# OZ440-SE100-CAR003_sheet5.net
KiCad netlist of a schematic drawn in Altium Designer
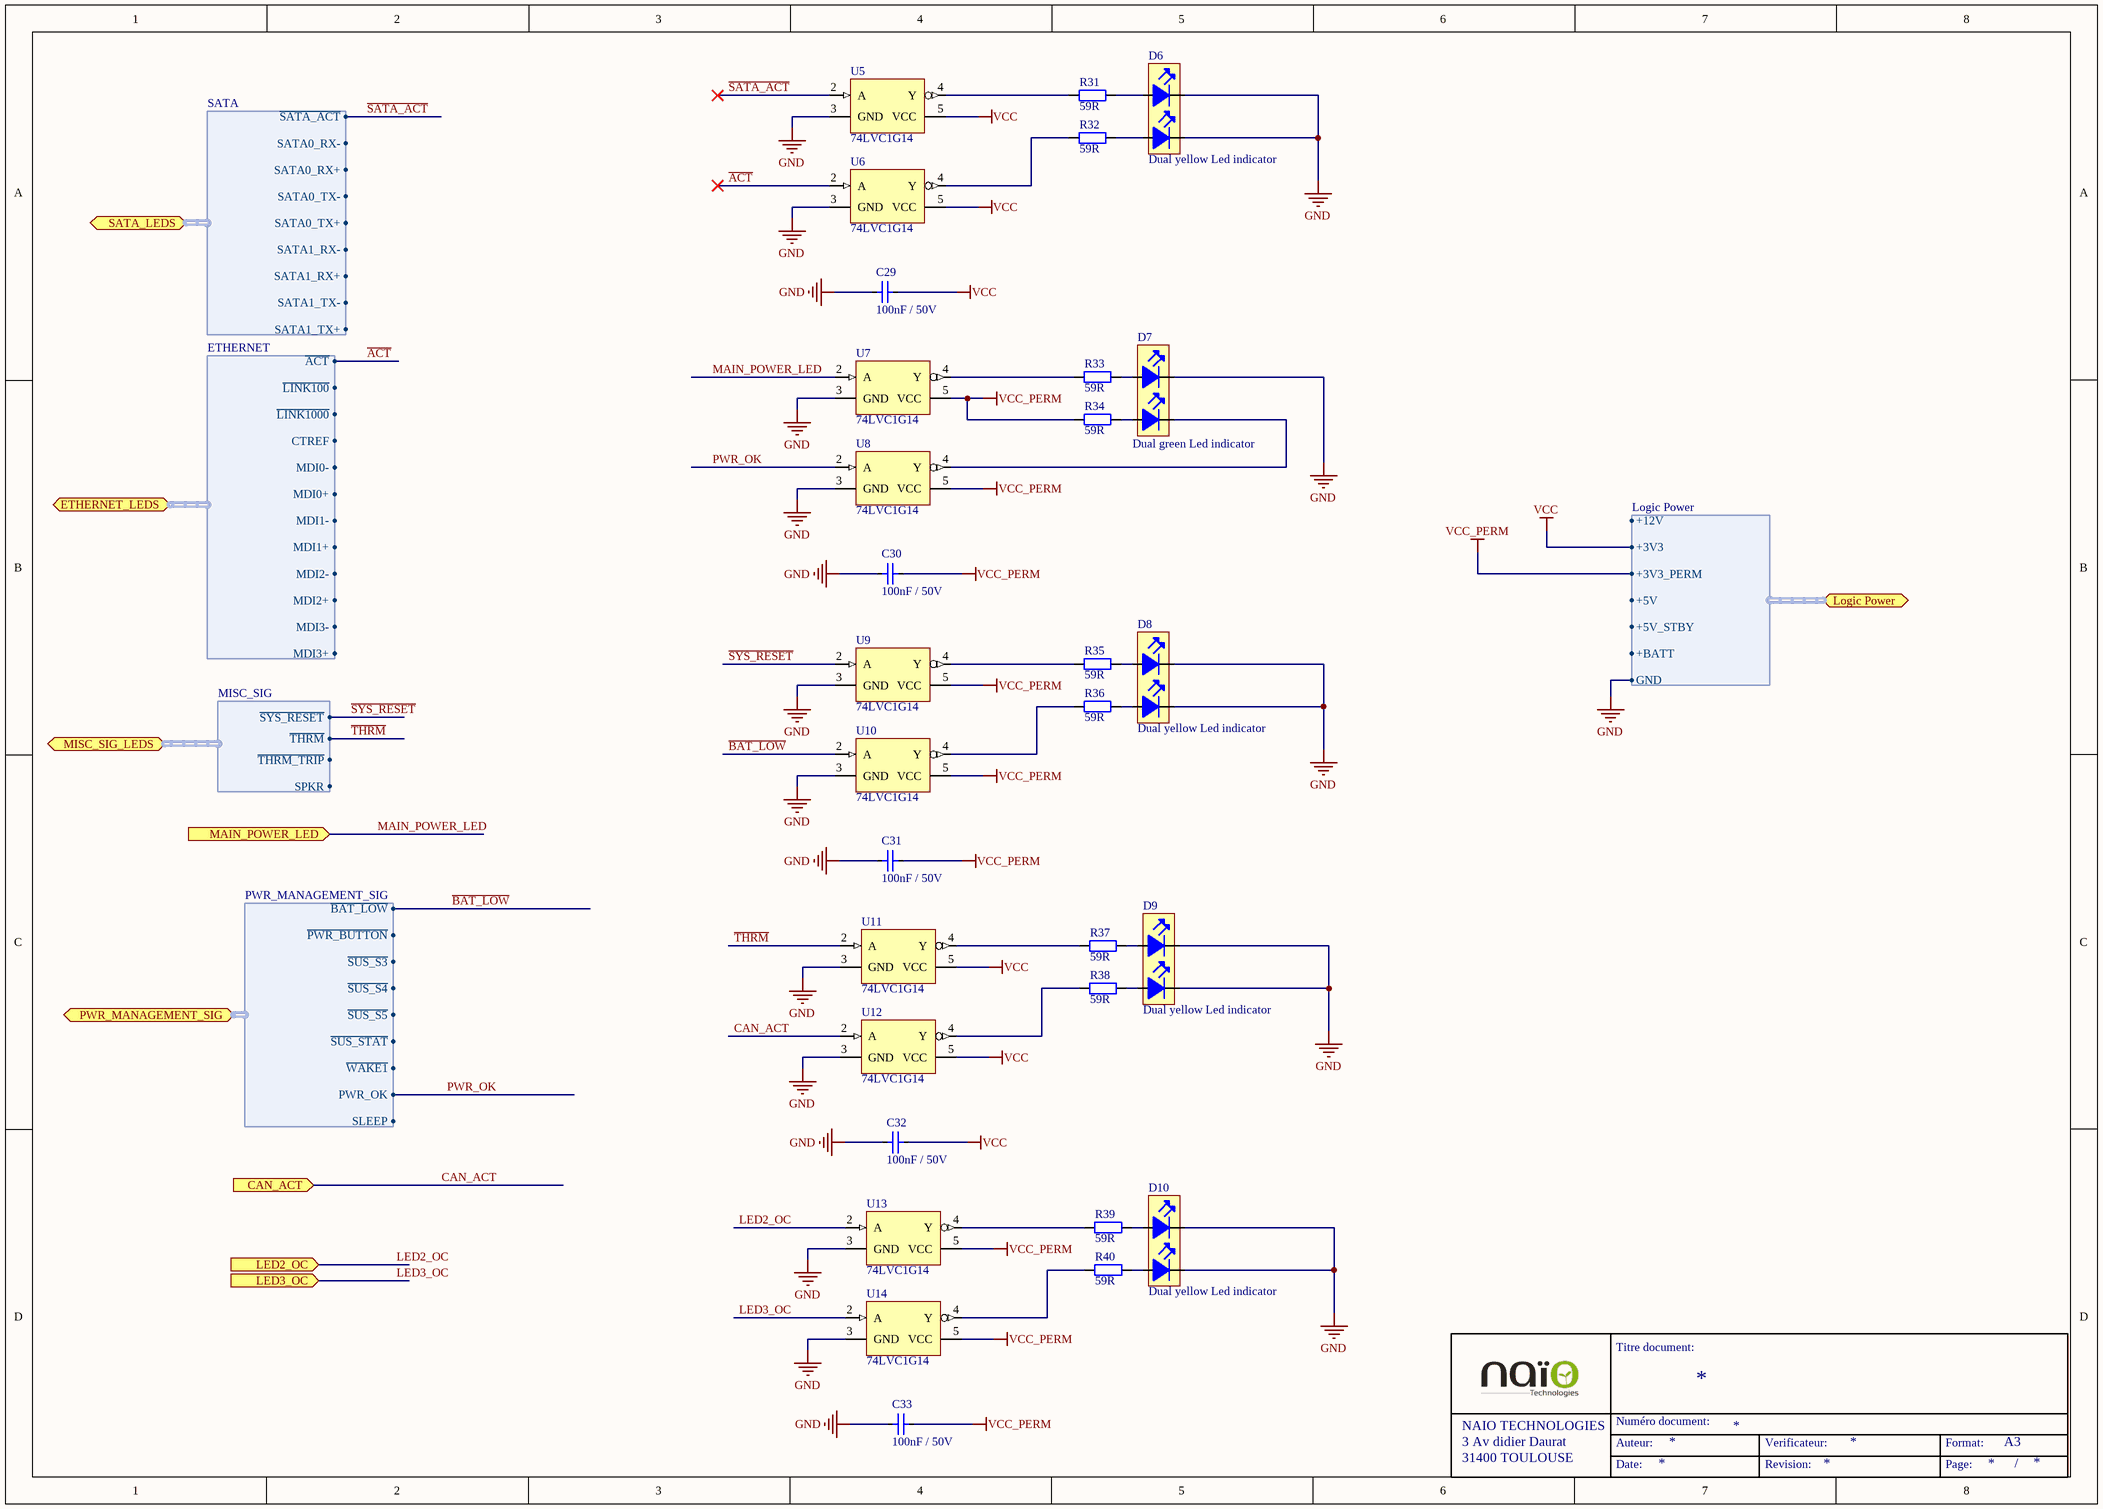
[diagram p0: OZ440-SE100-CAR003_sheet5.SchDoc]

(export (version "E")
  (design (tool "Eeschema 10.0.6"))
  (components
    (comp (ref "C29")
      (value "CAP-SMD")
      (footprint "C0805-STD")
      (description "0805 100nF / 50V  X7R ceramic capacitor")
      (fields
        (field (name "DISPLAYED REFERENCE") "100nF / 50V")
        (field (name "TOLERANCE") "+/- 10%")
        (field (name "MANUFACTURER") "vishay")
      )
      (libsource (lib "lib_NAIO") (part "CAP-SMD"))
    )
    (comp (ref "C30")
      (value "CAP-SMD")
      (footprint "C0805-STD")
      (description "0805 100nF / 50V  X7R ceramic capacitor")
      (fields
        (field (name "DISPLAYED REFERENCE") "100nF / 50V")
        (field (name "TOLERANCE") "+/- 10%")
        (field (name "MANUFACTURER") "vishay")
      )
      (libsource (lib "lib_NAIO") (part "CAP-SMD"))
    )
    (comp (ref "C31")
      (value "CAP-SMD")
      (footprint "C0805-STD")
      (description "0805 100nF / 50V  X7R ceramic capacitor")
      (fields
        (field (name "DISPLAYED REFERENCE") "100nF / 50V")
        (field (name "TOLERANCE") "+/- 10%")
        (field (name "MANUFACTURER") "vishay")
      )
      (libsource (lib "lib_NAIO") (part "CAP-SMD"))
    )
    (comp (ref "C32")
      (value "CAP-SMD")
      (footprint "C0805-STD")
      (description "0805 100nF / 50V  X7R ceramic capacitor")
      (fields
        (field (name "DISPLAYED REFERENCE") "100nF / 50V")
        (field (name "TOLERANCE") "+/- 10%")
        (field (name "MANUFACTURER") "vishay")
      )
      (libsource (lib "lib_NAIO") (part "CAP-SMD"))
    )
    (comp (ref "C33")
      (value "CAP-SMD")
      (footprint "C0805-STD")
      (description "0805 100nF / 50V  X7R ceramic capacitor")
      (fields
        (field (name "DISPLAYED REFERENCE") "100nF / 50V")
        (field (name "TOLERANCE") "+/- 10%")
        (field (name "MANUFACTURER") "vishay")
      )
      (libsource (lib "lib_NAIO") (part "CAP-SMD"))
    )
    (comp (ref "D6")
      (value "LED_DUAL")
      (footprint "LED_3MM_DUAL")
      (description "Dual Yellow led indicator")
      (fields
        (field (name "DISPLAYED REFERENCE") "Dual yellow Led indicator")
        (field (name "MANUFACTURER") "KINGBRIGHT")
      )
      (libsource (lib "lib_NAIO") (part "LED_DUAL"))
    )
    (comp (ref "D7")
      (value "LED_DUAL")
      (footprint "LED_3MM_DUAL")
      (description "Dual green led indicator")
      (fields
        (field (name "DISPLAYED REFERENCE") "Dual green Led indicator")
        (field (name "MANUFACTURER") "KINGBRIGHT")
      )
      (libsource (lib "lib_NAIO") (part "LED_DUAL"))
    )
    (comp (ref "D8")
      (value "LED_DUAL")
      (footprint "LED_3MM_DUAL")
      (description "Dual Yellow led indicator")
      (fields
        (field (name "DISPLAYED REFERENCE") "Dual yellow Led indicator")
        (field (name "MANUFACTURER") "KINGBRIGHT")
      )
      (libsource (lib "lib_NAIO") (part "LED_DUAL"))
    )
    (comp (ref "D9")
      (value "LED_DUAL")
      (footprint "LED_3MM_DUAL")
      (description "Dual Yellow led indicator")
      (fields
        (field (name "DISPLAYED REFERENCE") "Dual yellow Led indicator")
        (field (name "MANUFACTURER") "KINGBRIGHT")
      )
      (libsource (lib "lib_NAIO") (part "LED_DUAL"))
    )
    (comp (ref "D10")
      (value "LED_DUAL")
      (footprint "LED_3MM_DUAL")
      (description "Dual Yellow led indicator")
      (fields
        (field (name "DISPLAYED REFERENCE") "Dual yellow Led indicator")
        (field (name "MANUFACTURER") "KINGBRIGHT")
      )
      (libsource (lib "lib_NAIO") (part "LED_DUAL"))
    )
    (comp (ref "R31")
      (value "RES-SMD")
      (footprint "R0805-STD")
      (description "59 Ohm 0805 SMD resistor")
      (fields
        (field (name "DISPLAYED REFERENCE") "59R")
        (field (name "TOLERANCE") "1 %")
        (field (name "MANUFACTURER") "Vishay")
      )
      (libsource (lib "lib_NAIO") (part "RES-SMD"))
    )
    (comp (ref "R32")
      (value "RES-SMD")
      (footprint "R0805-STD")
      (description "59 Ohm 0805 SMD resistor")
      (fields
        (field (name "DISPLAYED REFERENCE") "59R")
        (field (name "TOLERANCE") "1 %")
        (field (name "MANUFACTURER") "Vishay")
      )
      (libsource (lib "lib_NAIO") (part "RES-SMD"))
    )
    (comp (ref "R33")
      (value "RES-SMD")
      (footprint "R0805-STD")
      (description "59 Ohm 0805 SMD resistor")
      (fields
        (field (name "DISPLAYED REFERENCE") "59R")
        (field (name "TOLERANCE") "1 %")
        (field (name "MANUFACTURER") "Vishay")
      )
      (libsource (lib "lib_NAIO") (part "RES-SMD"))
    )
    (comp (ref "R34")
      (value "RES-SMD")
      (footprint "R0805-STD")
      (description "59 Ohm 0805 SMD resistor")
      (fields
        (field (name "DISPLAYED REFERENCE") "59R")
        (field (name "TOLERANCE") "1 %")
        (field (name "MANUFACTURER") "Vishay")
      )
      (libsource (lib "lib_NAIO") (part "RES-SMD"))
    )
    (comp (ref "R35")
      (value "RES-SMD")
      (footprint "R0805-STD")
      (description "59 Ohm 0805 SMD resistor")
      (fields
        (field (name "DISPLAYED REFERENCE") "59R")
        (field (name "TOLERANCE") "1 %")
        (field (name "MANUFACTURER") "Vishay")
      )
      (libsource (lib "lib_NAIO") (part "RES-SMD"))
    )
    (comp (ref "R36")
      (value "RES-SMD")
      (footprint "R0805-STD")
      (description "59 Ohm 0805 SMD resistor")
      (fields
        (field (name "DISPLAYED REFERENCE") "59R")
        (field (name "TOLERANCE") "1 %")
        (field (name "MANUFACTURER") "Vishay")
      )
      (libsource (lib "lib_NAIO") (part "RES-SMD"))
    )
    (comp (ref "R37")
      (value "RES-SMD")
      (footprint "R0805-STD")
      (description "59 Ohm 0805 SMD resistor")
      (fields
        (field (name "DISPLAYED REFERENCE") "59R")
        (field (name "TOLERANCE") "1 %")
        (field (name "MANUFACTURER") "Vishay")
      )
      (libsource (lib "lib_NAIO") (part "RES-SMD"))
    )
    (comp (ref "R38")
      (value "RES-SMD")
      (footprint "R0805-STD")
      (description "59 Ohm 0805 SMD resistor")
      (fields
        (field (name "DISPLAYED REFERENCE") "59R")
        (field (name "TOLERANCE") "1 %")
        (field (name "MANUFACTURER") "Vishay")
      )
      (libsource (lib "lib_NAIO") (part "RES-SMD"))
    )
    (comp (ref "R39")
      (value "RES-SMD")
      (footprint "R0805-STD")
      (description "59 Ohm 0805 SMD resistor")
      (fields
        (field (name "DISPLAYED REFERENCE") "59R")
        (field (name "TOLERANCE") "1 %")
        (field (name "MANUFACTURER") "Vishay")
      )
      (libsource (lib "lib_NAIO") (part "RES-SMD"))
    )
    (comp (ref "R40")
      (value "RES-SMD")
      (footprint "R0805-STD")
      (description "59 Ohm 0805 SMD resistor")
      (fields
        (field (name "DISPLAYED REFERENCE") "59R")
        (field (name "TOLERANCE") "1 %")
        (field (name "MANUFACTURER") "Vishay")
      )
      (libsource (lib "lib_NAIO") (part "RES-SMD"))
    )
    (comp (ref "U5")
      (value "74xxx1G14GW-SOT353-1")
      (footprint "SOT353-1_5pin-STD")
      (description "smith trigger inverter")
      (fields (field (name "DISPLAYED REFERENCE") "74LVC1G14") (field (name "MANUFACTURER") "NXP"))
      (libsource (lib "lib_NAIO") (part "74xxx1G14GW-SOT353-1"))
    )
    (comp (ref "U6")
      (value "74xxx1G14GW-SOT353-1")
      (footprint "SOT353-1_5pin-STD")
      (description "smith trigger inverter")
      (fields (field (name "DISPLAYED REFERENCE") "74LVC1G14") (field (name "MANUFACTURER") "NXP"))
      (libsource (lib "lib_NAIO") (part "74xxx1G14GW-SOT353-1"))
    )
    (comp (ref "U7")
      (value "74xxx1G14GW-SOT353-1")
      (footprint "SOT353-1_5pin-STD")
      (description "smith trigger inverter")
      (fields (field (name "DISPLAYED REFERENCE") "74LVC1G14") (field (name "MANUFACTURER") "NXP"))
      (libsource (lib "lib_NAIO") (part "74xxx1G14GW-SOT353-1"))
    )
    (comp (ref "U8")
      (value "74xxx1G14GW-SOT353-1")
      (footprint "SOT353-1_5pin-STD")
      (description "smith trigger inverter")
      (fields (field (name "DISPLAYED REFERENCE") "74LVC1G14") (field (name "MANUFACTURER") "NXP"))
      (libsource (lib "lib_NAIO") (part "74xxx1G14GW-SOT353-1"))
    )
    (comp (ref "U9")
      (value "74xxx1G14GW-SOT353-1")
      (footprint "SOT353-1_5pin-STD")
      (description "smith trigger inverter")
      (fields (field (name "DISPLAYED REFERENCE") "74LVC1G14") (field (name "MANUFACTURER") "NXP"))
      (libsource (lib "lib_NAIO") (part "74xxx1G14GW-SOT353-1"))
    )
    (comp (ref "U10")
      (value "74xxx1G14GW-SOT353-1")
      (footprint "SOT353-1_5pin-STD")
      (description "smith trigger inverter")
      (fields (field (name "DISPLAYED REFERENCE") "74LVC1G14") (field (name "MANUFACTURER") "NXP"))
      (libsource (lib "lib_NAIO") (part "74xxx1G14GW-SOT353-1"))
    )
    (comp (ref "U11")
      (value "74xxx1G14GW-SOT353-1")
      (footprint "SOT353-1_5pin-STD")
      (description "smith trigger inverter")
      (fields (field (name "DISPLAYED REFERENCE") "74LVC1G14") (field (name "MANUFACTURER") "NXP"))
      (libsource (lib "lib_NAIO") (part "74xxx1G14GW-SOT353-1"))
    )
    (comp (ref "U12")
      (value "74xxx1G14GW-SOT353-1")
      (footprint "SOT353-1_5pin-STD")
      (description "smith trigger inverter")
      (fields (field (name "DISPLAYED REFERENCE") "74LVC1G14") (field (name "MANUFACTURER") "NXP"))
      (libsource (lib "lib_NAIO") (part "74xxx1G14GW-SOT353-1"))
    )
    (comp (ref "U13")
      (value "74xxx1G14GW-SOT353-1")
      (footprint "SOT353-1_5pin-STD")
      (description "smith trigger inverter")
      (fields (field (name "DISPLAYED REFERENCE") "74LVC1G14") (field (name "MANUFACTURER") "NXP"))
      (libsource (lib "lib_NAIO") (part "74xxx1G14GW-SOT353-1"))
    )
    (comp (ref "U14")
      (value "74xxx1G14GW-SOT353-1")
      (footprint "SOT353-1_5pin-STD")
      (description "smith trigger inverter")
      (fields (field (name "DISPLAYED REFERENCE") "74LVC1G14") (field (name "MANUFACTURER") "NXP"))
      (libsource (lib "lib_NAIO") (part "74xxx1G14GW-SOT353-1"))
    )
  )
  (nets
    (net (code "7") (name "/ACT") (class "Default")
      (node (ref "U6") (pin "2") (pinfunction "A_2") (pintype "input"))
    )
    (net (code "8") (name "/BAT_LOW") (class "Default")
      (node (ref "U10") (pin "2") (pinfunction "A_2") (pintype "input"))
    )
    (net (code "9") (name "/CAN_ACT") (class "Default")
      (node (ref "U12") (pin "2") (pinfunction "A_2") (pintype "input"))
    )
    (net (code "10") (name "/LED2_OC") (class "Default")
      (node (ref "U13") (pin "2") (pinfunction "A_2") (pintype "input"))
    )
    (net (code "11") (name "/LED3_OC") (class "Default")
      (node (ref "U14") (pin "2") (pinfunction "A_2") (pintype "input"))
    )
    (net (code "12") (name "/MAIN_POWER_LED") (class "Default")
      (node (ref "U7") (pin "2") (pinfunction "A_2") (pintype "input"))
    )
    (net (code "13") (name "/PWR_OK") (class "Default")
      (node (ref "U8") (pin "2") (pinfunction "A_2") (pintype "input"))
    )
    (net (code "14") (name "/SATA_ACT") (class "Default")
      (node (ref "U5") (pin "2") (pinfunction "A_2") (pintype "input+no_connect"))
    )
    (net (code "15") (name "/SYS_RESET") (class "Default")
      (node (ref "U9") (pin "2") (pinfunction "A_2") (pintype "input"))
    )
    (net (code "16") (name "/THRM") (class "Default")
      (node (ref "U11") (pin "2") (pinfunction "A_2") (pintype "input"))
    )
    (net (code "22") (name "GND") (class "Default")
      (node (ref "C29") (pin "1") (pinfunction "1_1") (pintype "passive"))
      (node (ref "C30") (pin "1") (pinfunction "1_1") (pintype "passive"))
      (node (ref "C31") (pin "1") (pinfunction "1_1") (pintype "passive"))
      (node (ref "C32") (pin "1") (pinfunction "1_1") (pintype "passive"))
      (node (ref "C33") (pin "1") (pinfunction "1_1") (pintype "passive"))
      (node (ref "D10") (pin "K1") (pinfunction "K1_K1") (pintype "passive"))
      (node (ref "D10") (pin "K2") (pinfunction "K2_K2") (pintype "passive"))
      (node (ref "D6") (pin "K1") (pinfunction "K1_K1") (pintype "passive"))
      (node (ref "D6") (pin "K2") (pinfunction "K2_K2") (pintype "passive"))
      (node (ref "D7") (pin "K1") (pinfunction "K1_K1") (pintype "passive"))
      (node (ref "D8") (pin "K1") (pinfunction "K1_K1") (pintype "passive"))
      (node (ref "D8") (pin "K2") (pinfunction "K2_K2") (pintype "passive"))
      (node (ref "D9") (pin "K1") (pinfunction "K1_K1") (pintype "passive"))
      (node (ref "D9") (pin "K2") (pinfunction "K2_K2") (pintype "passive"))
      (node (ref "U10") (pin "3") (pinfunction "GND_3") (pintype "power_in"))
      (node (ref "U11") (pin "3") (pinfunction "GND_3") (pintype "power_in"))
      (node (ref "U12") (pin "3") (pinfunction "GND_3") (pintype "power_in"))
      (node (ref "U13") (pin "3") (pinfunction "GND_3") (pintype "power_in"))
      (node (ref "U14") (pin "3") (pinfunction "GND_3") (pintype "power_in"))
      (node (ref "U5") (pin "3") (pinfunction "GND_3") (pintype "power_in"))
      (node (ref "U6") (pin "3") (pinfunction "GND_3") (pintype "power_in"))
      (node (ref "U7") (pin "3") (pinfunction "GND_3") (pintype "power_in"))
      (node (ref "U8") (pin "3") (pinfunction "GND_3") (pintype "power_in"))
      (node (ref "U9") (pin "3") (pinfunction "GND_3") (pintype "power_in"))
    )
    (net (code "23") (name "Net-(D6-PadA1)") (class "Default")
      (node (ref "D6") (pin "A1") (pinfunction "A1_A1") (pintype "passive"))
      (node (ref "R31") (pin "2") (pinfunction "2_2") (pintype "passive"))
    )
    (net (code "24") (name "Net-(D6-PadA2)") (class "Default")
      (node (ref "D6") (pin "A2") (pinfunction "A2_A2") (pintype "passive"))
      (node (ref "R32") (pin "2") (pinfunction "2_2") (pintype "passive"))
    )
    (net (code "25") (name "Net-(D7-PadA1)") (class "Default")
      (node (ref "D7") (pin "A1") (pinfunction "A1_A1") (pintype "passive"))
      (node (ref "R33") (pin "2") (pinfunction "2_2") (pintype "passive"))
    )
    (net (code "26") (name "Net-(D7-PadA2)") (class "Default")
      (node (ref "D7") (pin "A2") (pinfunction "A2_A2") (pintype "passive"))
      (node (ref "R34") (pin "2") (pinfunction "2_2") (pintype "passive"))
    )
    (net (code "27") (name "Net-(D8-PadA1)") (class "Default")
      (node (ref "D8") (pin "A1") (pinfunction "A1_A1") (pintype "passive"))
      (node (ref "R35") (pin "2") (pinfunction "2_2") (pintype "passive"))
    )
    (net (code "28") (name "Net-(D8-PadA2)") (class "Default")
      (node (ref "D8") (pin "A2") (pinfunction "A2_A2") (pintype "passive"))
      (node (ref "R36") (pin "2") (pinfunction "2_2") (pintype "passive"))
    )
    (net (code "29") (name "Net-(D9-PadA1)") (class "Default")
      (node (ref "D9") (pin "A1") (pinfunction "A1_A1") (pintype "passive"))
      (node (ref "R37") (pin "2") (pinfunction "2_2") (pintype "passive"))
    )
    (net (code "30") (name "Net-(D9-PadA2)") (class "Default")
      (node (ref "D9") (pin "A2") (pinfunction "A2_A2") (pintype "passive"))
      (node (ref "R38") (pin "2") (pinfunction "2_2") (pintype "passive"))
    )
    (net (code "31") (name "Net-(D10-PadA1)") (class "Default")
      (node (ref "D10") (pin "A1") (pinfunction "A1_A1") (pintype "passive"))
      (node (ref "R39") (pin "2") (pinfunction "2_2") (pintype "passive"))
    )
    (net (code "32") (name "Net-(D10-PadA2)") (class "Default")
      (node (ref "D10") (pin "A2") (pinfunction "A2_A2") (pintype "passive"))
      (node (ref "R40") (pin "2") (pinfunction "2_2") (pintype "passive"))
    )
    (net (code "33") (name "Net-(U5-Y)") (class "Default")
      (node (ref "R31") (pin "1") (pinfunction "1_1") (pintype "passive"))
      (node (ref "U5") (pin "4") (pinfunction "Y_4") (pintype "output"))
    )
    (net (code "34") (name "Net-(U6-Y)") (class "Default")
      (node (ref "R32") (pin "1") (pinfunction "1_1") (pintype "passive"))
      (node (ref "U6") (pin "4") (pinfunction "Y_4") (pintype "output"))
    )
    (net (code "35") (name "Net-(U7-Y)") (class "Default")
      (node (ref "R33") (pin "1") (pinfunction "1_1") (pintype "passive"))
      (node (ref "U7") (pin "4") (pinfunction "Y_4") (pintype "output"))
    )
    (net (code "36") (name "Net-(U8-Y)") (class "Default")
      (node (ref "D7") (pin "K2") (pinfunction "K2_K2") (pintype "passive"))
      (node (ref "U8") (pin "4") (pinfunction "Y_4") (pintype "output"))
    )
    (net (code "37") (name "Net-(U9-Y)") (class "Default")
      (node (ref "R35") (pin "1") (pinfunction "1_1") (pintype "passive"))
      (node (ref "U9") (pin "4") (pinfunction "Y_4") (pintype "output"))
    )
    (net (code "38") (name "Net-(U10-Y)") (class "Default")
      (node (ref "R36") (pin "1") (pinfunction "1_1") (pintype "passive"))
      (node (ref "U10") (pin "4") (pinfunction "Y_4") (pintype "output"))
    )
    (net (code "39") (name "Net-(U11-Y)") (class "Default")
      (node (ref "R37") (pin "1") (pinfunction "1_1") (pintype "passive"))
      (node (ref "U11") (pin "4") (pinfunction "Y_4") (pintype "output"))
    )
    (net (code "40") (name "Net-(U12-Y)") (class "Default")
      (node (ref "R38") (pin "1") (pinfunction "1_1") (pintype "passive"))
      (node (ref "U12") (pin "4") (pinfunction "Y_4") (pintype "output"))
    )
    (net (code "41") (name "Net-(U13-Y)") (class "Default")
      (node (ref "R39") (pin "1") (pinfunction "1_1") (pintype "passive"))
      (node (ref "U13") (pin "4") (pinfunction "Y_4") (pintype "output"))
    )
    (net (code "42") (name "Net-(U14-Y)") (class "Default")
      (node (ref "R40") (pin "1") (pinfunction "1_1") (pintype "passive"))
      (node (ref "U14") (pin "4") (pinfunction "Y_4") (pintype "output"))
    )
    (net (code "43") (name "VCC") (class "Default")
      (node (ref "C29") (pin "2") (pinfunction "2_2") (pintype "passive"))
      (node (ref "C32") (pin "2") (pinfunction "2_2") (pintype "passive"))
      (node (ref "U11") (pin "5") (pinfunction "VCC_5") (pintype "power_in"))
      (node (ref "U12") (pin "5") (pinfunction "VCC_5") (pintype "power_in"))
      (node (ref "U5") (pin "5") (pinfunction "VCC_5") (pintype "power_in"))
      (node (ref "U6") (pin "5") (pinfunction "VCC_5") (pintype "power_in"))
    )
    (net (code "44") (name "VCC_PERM") (class "Default")
      (node (ref "C30") (pin "2") (pinfunction "2_2") (pintype "passive"))
      (node (ref "C31") (pin "2") (pinfunction "2_2") (pintype "passive"))
      (node (ref "C33") (pin "2") (pinfunction "2_2") (pintype "passive"))
      (node (ref "R34") (pin "1") (pinfunction "1_1") (pintype "passive"))
      (node (ref "U10") (pin "5") (pinfunction "VCC_5") (pintype "power_in"))
      (node (ref "U13") (pin "5") (pinfunction "VCC_5") (pintype "power_in"))
      (node (ref "U14") (pin "5") (pinfunction "VCC_5") (pintype "power_in"))
      (node (ref "U7") (pin "5") (pinfunction "VCC_5") (pintype "power_in"))
      (node (ref "U8") (pin "5") (pinfunction "VCC_5") (pintype "power_in"))
      (node (ref "U9") (pin "5") (pinfunction "VCC_5") (pintype "power_in"))
    )
  )
)
